# PCB_Tutorial.net
KiCad netlist of a schematic drawn in EAGLE
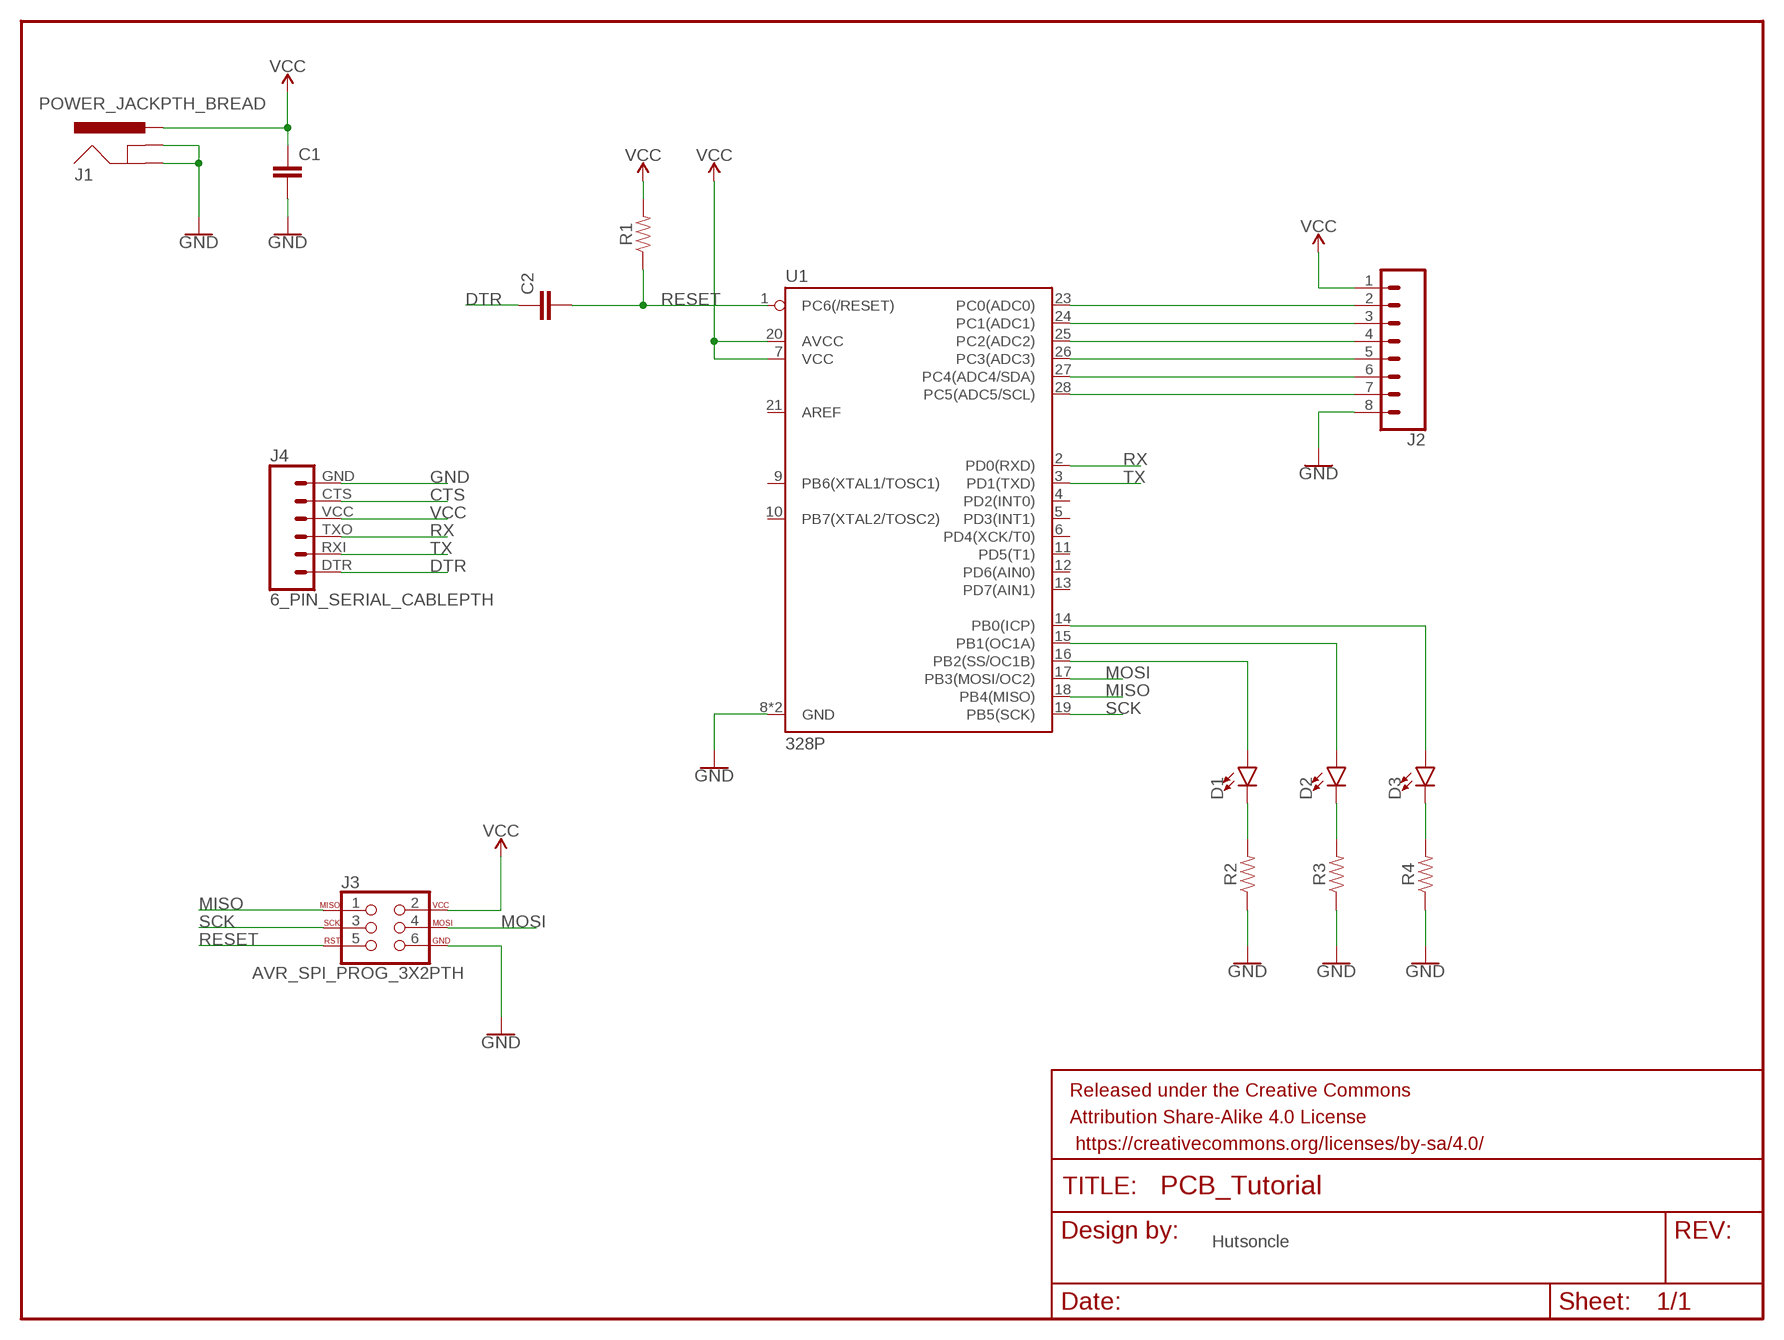
[diagram p0: schematic, sheet 1]

(export (version "E")
  (design (tool "Eeschema 10.0.6"))
  (components
    (comp (ref "C1")
      (value "0.1uF")
      (footprint "eagle-import:CAP-PTH-SMALL-KIT")
      (libsource (lib "eagle-import") (part "0.1UF-KIT-EZ-50V-20%"))
    )
    (comp (ref "C2")
      (value "0.1uF")
      (footprint "eagle-import:CAP-PTH-SMALL-KIT")
      (libsource (lib "eagle-import") (part "0.1UF-KIT-EZ-50V-20%"))
    )
    (comp (ref "D1")
      (value "LED5MM")
      (footprint "eagle-import:LED_5MM")
      (libsource (lib "eagle-import") (part "LED5MM"))
    )
    (comp (ref "D2")
      (value "LED5MM")
      (footprint "eagle-import:LED_5MM")
      (libsource (lib "eagle-import") (part "LED5MM"))
    )
    (comp (ref "D3")
      (value "LED5MM")
      (footprint "eagle-import:LED_5MM")
      (libsource (lib "eagle-import") (part "LED5MM"))
    )
    (comp (ref "FRAME1")
      (value "FRAME-LETTER")
      (footprint "eagle-import:CREATIVE_COMMONS")
      (libsource (lib "eagle-import") (part "FRAME-LETTER"))
    )
    (comp (ref "J1")
      (value "POWER_JACKPTH_BREAD")
      (footprint "eagle-import:POWER_JACK_PTH_BREAD")
      (libsource (lib "eagle-import") (part "POWER_JACKPTH_BREAD"))
    )
    (comp (ref "J2")
      (value "CONN_08\"")
      (footprint "eagle-import:1X08")
      (libsource (lib "eagle-import") (part "CONN_08{dblquote}"))
    )
    (comp (ref "J3")
      (value "AVR_SPI_PROG_3X2PTH")
      (footprint "eagle-import:2X3")
      (libsource (lib "eagle-import") (part "AVR_SPI_PROG_3X2PTH"))
    )
    (comp (ref "J4")
      (value "6_PIN_SERIAL_CABLEPTH")
      (footprint "eagle-import:FTDI_BASIC")
      (libsource (lib "eagle-import") (part "6_PIN_SERIAL_CABLEPTH"))
    )
    (comp (ref "R1")
      (value "RESISTORAXIAL-0.3")
      (footprint "eagle-import:AXIAL-0.3")
      (libsource (lib "eagle-import") (part "RESISTORAXIAL-0.3"))
    )
    (comp (ref "R2")
      (value "RESISTORAXIAL-0.3")
      (footprint "eagle-import:AXIAL-0.3")
      (libsource (lib "eagle-import") (part "RESISTORAXIAL-0.3"))
    )
    (comp (ref "R3")
      (value "RESISTORAXIAL-0.3")
      (footprint "eagle-import:AXIAL-0.3")
      (libsource (lib "eagle-import") (part "RESISTORAXIAL-0.3"))
    )
    (comp (ref "R4")
      (value "RESISTORAXIAL-0.3")
      (footprint "eagle-import:AXIAL-0.3")
      (libsource (lib "eagle-import") (part "RESISTORAXIAL-0.3"))
    )
    (comp (ref "U1")
      (value "328P")
      (footprint "eagle-import:DIP28")
      (libsource (lib "eagle-import") (part "ATMEGA328P_PDIP"))
    )
  )
  (nets
    (net (code "1") (name "/CTS") (class "Default")
      (node (ref "J4") (pin "CTS") (pinfunction "5_CTS") (pintype "passive"))
    )
    (net (code "2") (name "/DTR") (class "Default")
      (node (ref "C2") (pin "1") (pinfunction "1_1") (pintype "passive"))
      (node (ref "J4") (pin "DTR") (pinfunction "1_DTR") (pintype "passive"))
    )
    (net (code "3") (name "/MISO") (class "Default")
      (node (ref "J3") (pin "1") (pinfunction "1_1") (pintype "passive"))
      (node (ref "U1") (pin "18") (pinfunction "PB4(MISO)_18") (pintype "bidirectional"))
    )
    (net (code "4") (name "/MOSI") (class "Default")
      (node (ref "J3") (pin "4") (pinfunction "4_4") (pintype "passive"))
      (node (ref "U1") (pin "17") (pinfunction "PB3(MOSI/OC2)_17") (pintype "bidirectional"))
    )
    (net (code "5") (name "/RESET") (class "Default")
      (node (ref "C2") (pin "2") (pinfunction "2_2") (pintype "passive"))
      (node (ref "J3") (pin "5") (pinfunction "5_5") (pintype "passive"))
      (node (ref "R1") (pin "P$1") (pinfunction "1_P$1") (pintype "passive"))
      (node (ref "U1") (pin "1") (pinfunction "PC6(/RESET)_1") (pintype "bidirectional"))
    )
    (net (code "6") (name "/RX") (class "Default")
      (node (ref "J4") (pin "TXO") (pinfunction "3_TXO") (pintype "passive"))
      (node (ref "U1") (pin "2") (pinfunction "PD0(RXD)_2") (pintype "bidirectional"))
    )
    (net (code "7") (name "/SCK") (class "Default")
      (node (ref "J3") (pin "3") (pinfunction "3_3") (pintype "passive"))
      (node (ref "U1") (pin "19") (pinfunction "PB5(SCK)_19") (pintype "bidirectional"))
    )
    (net (code "8") (name "/TX") (class "Default")
      (node (ref "J4") (pin "RXI") (pinfunction "2_RXI") (pintype "passive"))
      (node (ref "U1") (pin "3") (pinfunction "PD1(TXD)_3") (pintype "bidirectional"))
    )
    (net (code "9") (name "GND") (class "Default")
      (node (ref "C1") (pin "2") (pinfunction "2_2") (pintype "passive"))
      (node (ref "J1") (pin "GND") (pinfunction "GND_GND") (pintype "bidirectional"))
      (node (ref "J1") (pin "GNDBREAK") (pinfunction "GNDBREAK_GNDBREAK") (pintype "bidirectional"))
      (node (ref "J2") (pin "8") (pinfunction "8_8") (pintype "passive"))
      (node (ref "J3") (pin "6") (pinfunction "6_6") (pintype "passive"))
      (node (ref "J4") (pin "GND") (pinfunction "6_GND") (pintype "passive"))
      (node (ref "R2") (pin "P$1") (pinfunction "1_P$1") (pintype "passive"))
      (node (ref "R3") (pin "P$1") (pinfunction "1_P$1") (pintype "passive"))
      (node (ref "R4") (pin "P$1") (pinfunction "1_P$1") (pintype "passive"))
      (node (ref "U1") (pin "22") (pinfunction "GND_22") (pintype "bidirectional"))
      (node (ref "U1") (pin "8") (pinfunction "GND_8") (pintype "bidirectional"))
    )
    (net (code "10") (name "Net-(D1-C)") (class "Default")
      (node (ref "D1") (pin "K") (pinfunction "C_K") (pintype "passive"))
      (node (ref "R2") (pin "P$2") (pinfunction "2_P$2") (pintype "passive"))
    )
    (net (code "11") (name "Net-(D2-C)") (class "Default")
      (node (ref "D2") (pin "K") (pinfunction "C_K") (pintype "passive"))
      (node (ref "R3") (pin "P$2") (pinfunction "2_P$2") (pintype "passive"))
    )
    (net (code "12") (name "Net-(D3-C)") (class "Default")
      (node (ref "D3") (pin "K") (pinfunction "C_K") (pintype "passive"))
      (node (ref "R4") (pin "P$2") (pinfunction "2_P$2") (pintype "passive"))
    )
    (net (code "13") (name "Net-(U1-PB0(ICP))") (class "Default")
      (node (ref "D3") (pin "A") (pinfunction "A_A") (pintype "passive"))
      (node (ref "U1") (pin "14") (pinfunction "PB0(ICP)_14") (pintype "bidirectional"))
    )
    (net (code "14") (name "Net-(U1-PB1(OC1A))") (class "Default")
      (node (ref "D2") (pin "A") (pinfunction "A_A") (pintype "passive"))
      (node (ref "U1") (pin "15") (pinfunction "PB1(OC1A)_15") (pintype "bidirectional"))
    )
    (net (code "15") (name "Net-(U1-PB2(SS{slash}OC1B))") (class "Default")
      (node (ref "D1") (pin "A") (pinfunction "A_A") (pintype "passive"))
      (node (ref "U1") (pin "16") (pinfunction "PB2(SS/OC1B)_16") (pintype "bidirectional"))
    )
    (net (code "16") (name "Net-(U1-PC0(ADC0))") (class "Default")
      (node (ref "J2") (pin "2") (pinfunction "2_2") (pintype "passive"))
      (node (ref "U1") (pin "23") (pinfunction "PC0(ADC0)_23") (pintype "bidirectional"))
    )
    (net (code "17") (name "Net-(U1-PC1(ADC1))") (class "Default")
      (node (ref "J2") (pin "3") (pinfunction "3_3") (pintype "passive"))
      (node (ref "U1") (pin "24") (pinfunction "PC1(ADC1)_24") (pintype "bidirectional"))
    )
    (net (code "18") (name "Net-(U1-PC2(ADC2))") (class "Default")
      (node (ref "J2") (pin "4") (pinfunction "4_4") (pintype "passive"))
      (node (ref "U1") (pin "25") (pinfunction "PC2(ADC2)_25") (pintype "bidirectional"))
    )
    (net (code "19") (name "Net-(U1-PC3(ADC3))") (class "Default")
      (node (ref "J2") (pin "5") (pinfunction "5_5") (pintype "passive"))
      (node (ref "U1") (pin "26") (pinfunction "PC3(ADC3)_26") (pintype "bidirectional"))
    )
    (net (code "20") (name "Net-(U1-PC4(ADC4{slash}SDA))") (class "Default")
      (node (ref "J2") (pin "6") (pinfunction "6_6") (pintype "passive"))
      (node (ref "U1") (pin "27") (pinfunction "PC4(ADC4/SDA)_27") (pintype "bidirectional"))
    )
    (net (code "21") (name "Net-(U1-PC5(ADC5{slash}SCL))") (class "Default")
      (node (ref "J2") (pin "7") (pinfunction "7_7") (pintype "passive"))
      (node (ref "U1") (pin "28") (pinfunction "PC5(ADC5/SCL)_28") (pintype "bidirectional"))
    )
    (net (code "22") (name "VCC") (class "Default")
      (node (ref "C1") (pin "1") (pinfunction "1_1") (pintype "passive"))
      (node (ref "J1") (pin "PWR") (pinfunction "PWR_PWR") (pintype "bidirectional"))
      (node (ref "J2") (pin "1") (pinfunction "1_1") (pintype "passive"))
      (node (ref "J3") (pin "2") (pinfunction "2_2") (pintype "passive"))
      (node (ref "J4") (pin "VCC") (pinfunction "4_VCC") (pintype "passive"))
      (node (ref "R1") (pin "P$2") (pinfunction "2_P$2") (pintype "passive"))
      (node (ref "U1") (pin "20") (pinfunction "AVCC_20") (pintype "bidirectional"))
      (node (ref "U1") (pin "7") (pinfunction "VCC_7") (pintype "bidirectional"))
    )
    (net (code "23") (name "unconnected-(U1-AREF-Pad21)") (class "Default")
      (node (ref "U1") (pin "21") (pinfunction "AREF_21") (pintype "bidirectional"))
    )
    (net (code "24") (name "unconnected-(U1-PB6(XTAL1{slash}TOSC1)-Pad9)") (class "Default")
      (node (ref "U1") (pin "9") (pinfunction "PB6(XTAL1/TOSC1)_9") (pintype "bidirectional"))
    )
    (net (code "25") (name "unconnected-(U1-PB7(XTAL2{slash}TOSC2)-Pad10)") (class "Default")
      (node (ref "U1") (pin "10") (pinfunction "PB7(XTAL2/TOSC2)_10") (pintype "bidirectional"))
    )
    (net (code "26") (name "unconnected-(U1-PD2(INT0)-Pad4)") (class "Default")
      (node (ref "U1") (pin "4") (pinfunction "PD2(INT0)_4") (pintype "bidirectional"))
    )
    (net (code "27") (name "unconnected-(U1-PD3(INT1)-Pad5)") (class "Default")
      (node (ref "U1") (pin "5") (pinfunction "PD3(INT1)_5") (pintype "bidirectional"))
    )
    (net (code "28") (name "unconnected-(U1-PD4(XCK{slash}T0)-Pad6)") (class "Default")
      (node (ref "U1") (pin "6") (pinfunction "PD4(XCK/T0)_6") (pintype "bidirectional"))
    )
    (net (code "29") (name "unconnected-(U1-PD5(T1)-Pad11)") (class "Default")
      (node (ref "U1") (pin "11") (pinfunction "PD5(T1)_11") (pintype "bidirectional"))
    )
    (net (code "30") (name "unconnected-(U1-PD6(AIN0)-Pad12)") (class "Default")
      (node (ref "U1") (pin "12") (pinfunction "PD6(AIN0)_12") (pintype "bidirectional"))
    )
    (net (code "31") (name "unconnected-(U1-PD7(AIN1)-Pad13)") (class "Default")
      (node (ref "U1") (pin "13") (pinfunction "PD7(AIN1)_13") (pintype "bidirectional"))
    )
  )
)
